# bd2.net
KiCad netlist of a schematic drawn in EAGLE
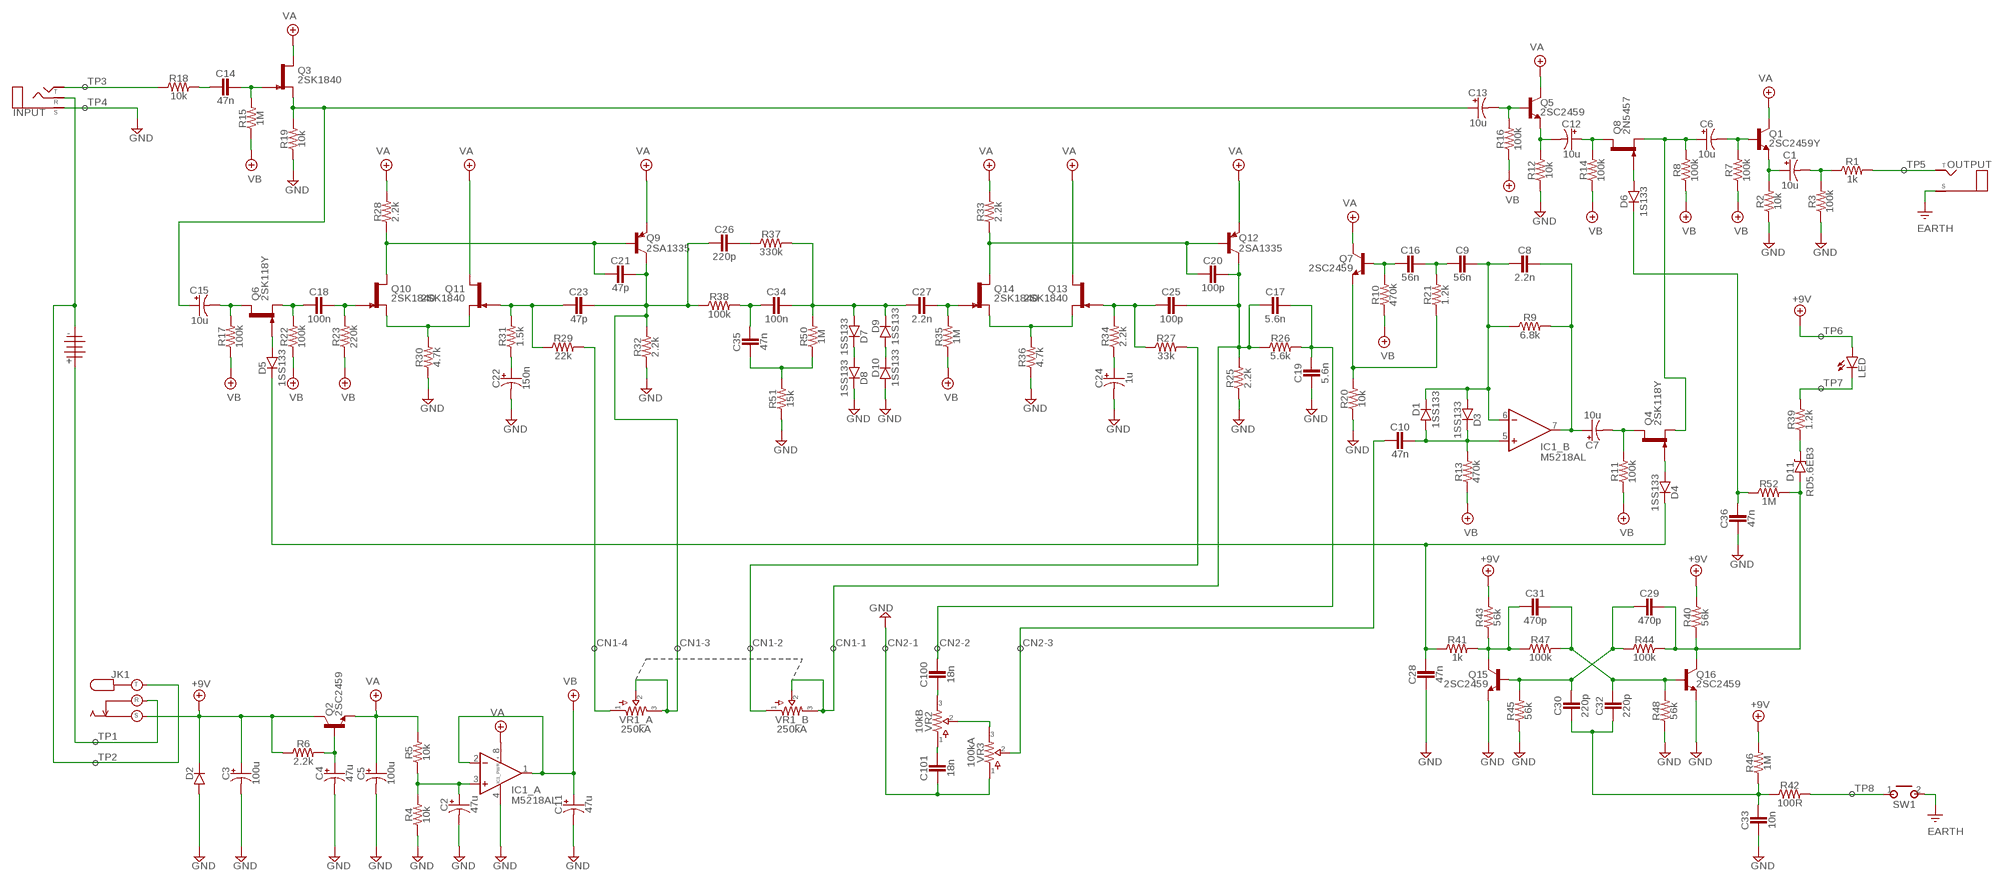
[diagram p0: schematic, sheet 1]

(export (version "E")
  (design (tool "Eeschema 10.0.6"))
  (components
    (comp (ref "BATTERY")
      (value "BATTERY")
      (footprint "eagle-import:TWO_PADS")
      (libsource (lib "eagle-import") (part "BATTERY"))
    )
    (comp (ref "C1")
      (value "10u")
      (footprint "eagle-import:040_020")
      (libsource (lib "eagle-import") (part "0400"))
    )
    (comp (ref "C2")
      (value "47u")
      (footprint "eagle-import:040_020")
      (libsource (lib "eagle-import") (part "0400"))
    )
    (comp (ref "C3")
      (value "100u")
      (footprint "eagle-import:040_020")
      (libsource (lib "eagle-import") (part "0400"))
    )
    (comp (ref "C4")
      (value "47u")
      (footprint "eagle-import:040_020")
      (libsource (lib "eagle-import") (part "0400"))
    )
    (comp (ref "C5")
      (value "100u")
      (footprint "eagle-import:040_020")
      (libsource (lib "eagle-import") (part "0400"))
    )
    (comp (ref "C6")
      (value "10u")
      (footprint "eagle-import:040_020")
      (libsource (lib "eagle-import") (part "0400"))
    )
    (comp (ref "C7")
      (value "10u")
      (footprint "eagle-import:040_020")
      (libsource (lib "eagle-import") (part "0400"))
    )
    (comp (ref "C8")
      (value "2.2n")
      (footprint "eagle-import:BOX_SMALL")
      (libsource (lib "eagle-import") (part "CER/FILMBOX.1"))
    )
    (comp (ref "C9")
      (value "56n")
      (footprint "eagle-import:BOX_SMALL")
      (libsource (lib "eagle-import") (part "CER/FILMBOX.1"))
    )
    (comp (ref "C10")
      (value "47n")
      (footprint "eagle-import:BOX_SMALL")
      (libsource (lib "eagle-import") (part "CER/FILMBOX.1"))
    )
    (comp (ref "C11")
      (value "47u")
      (footprint "eagle-import:040_020")
      (libsource (lib "eagle-import") (part "0400"))
    )
    (comp (ref "C12")
      (value "10u")
      (footprint "eagle-import:040_020")
      (libsource (lib "eagle-import") (part "0400"))
    )
    (comp (ref "C13")
      (value "10u")
      (footprint "eagle-import:040_020")
      (libsource (lib "eagle-import") (part "0400"))
    )
    (comp (ref "C14")
      (value "47n")
      (footprint "eagle-import:BOX_SMALL")
      (libsource (lib "eagle-import") (part "CER/FILMBOX.1"))
    )
    (comp (ref "C15")
      (value "10u")
      (footprint "eagle-import:040_020")
      (libsource (lib "eagle-import") (part "0400"))
    )
    (comp (ref "C16")
      (value "56n")
      (footprint "eagle-import:BOX_SMALL")
      (libsource (lib "eagle-import") (part "CER/FILMBOX.1"))
    )
    (comp (ref "C17")
      (value "5.6n")
      (footprint "eagle-import:BOX_SMALL")
      (libsource (lib "eagle-import") (part "CER/FILMBOX.1"))
    )
    (comp (ref "C18")
      (value "100n")
      (footprint "eagle-import:BOX_SMALL")
      (libsource (lib "eagle-import") (part "CER/FILMBOX.1"))
    )
    (comp (ref "C19")
      (value "5.6n")
      (footprint "eagle-import:BOX_SMALL")
      (libsource (lib "eagle-import") (part "CER/FILMBOX.1"))
    )
    (comp (ref "C20")
      (value "100p")
      (footprint "eagle-import:BOX_SMALL")
      (libsource (lib "eagle-import") (part "CER/FILMBOX.1"))
    )
    (comp (ref "C21")
      (value "47p")
      (footprint "eagle-import:BOX_SMALL")
      (libsource (lib "eagle-import") (part "CER/FILMBOX.1"))
    )
    (comp (ref "C22")
      (value "150n")
      (footprint "eagle-import:040_020")
      (libsource (lib "eagle-import") (part "0400"))
    )
    (comp (ref "C23")
      (value "47p")
      (footprint "eagle-import:BOX_SMALL")
      (libsource (lib "eagle-import") (part "CER/FILMBOX.1"))
    )
    (comp (ref "C24")
      (value "1u")
      (footprint "eagle-import:040_020")
      (libsource (lib "eagle-import") (part "0400"))
    )
    (comp (ref "C25")
      (value "100p")
      (footprint "eagle-import:BOX_SMALL")
      (libsource (lib "eagle-import") (part "CER/FILMBOX.1"))
    )
    (comp (ref "C26")
      (value "220p")
      (footprint "eagle-import:BOX_SMALL")
      (libsource (lib "eagle-import") (part "CER/FILMBOX.1"))
    )
    (comp (ref "C27")
      (value "2.2n")
      (footprint "eagle-import:BOX_SMALL")
      (libsource (lib "eagle-import") (part "CER/FILMBOX.1"))
    )
    (comp (ref "C28")
      (value "47n")
      (footprint "eagle-import:BOX_SMALL")
      (libsource (lib "eagle-import") (part "CER/FILMBOX.1"))
    )
    (comp (ref "C29")
      (value "470p")
      (footprint "eagle-import:BOX_SMALL")
      (libsource (lib "eagle-import") (part "CER/FILMBOX.1"))
    )
    (comp (ref "C30")
      (value "220p")
      (footprint "eagle-import:BOX_SMALL")
      (libsource (lib "eagle-import") (part "CER/FILMBOX.1"))
    )
    (comp (ref "C31")
      (value "470p")
      (footprint "eagle-import:BOX_SMALL")
      (libsource (lib "eagle-import") (part "CER/FILMBOX.1"))
    )
    (comp (ref "C32")
      (value "220p")
      (footprint "eagle-import:BOX_SMALL")
      (libsource (lib "eagle-import") (part "CER/FILMBOX.1"))
    )
    (comp (ref "C33")
      (value "10n")
      (footprint "eagle-import:BOX_SMALL")
      (libsource (lib "eagle-import") (part "CER/FILMBOX.1"))
    )
    (comp (ref "C34")
      (value "100n")
      (footprint "eagle-import:BOX_SMALL")
      (libsource (lib "eagle-import") (part "CER/FILMBOX.1"))
    )
    (comp (ref "C35")
      (value "47n")
      (footprint "eagle-import:BOX_SMALL")
      (libsource (lib "eagle-import") (part "CER/FILMBOX.1"))
    )
    (comp (ref "C36")
      (value "47n")
      (footprint "eagle-import:BOX_SMALL")
      (libsource (lib "eagle-import") (part "CER/FILMBOX.1"))
    )
    (comp (ref "C100")
      (value "18n")
      (footprint "eagle-import:BOX_SMALL")
      (libsource (lib "eagle-import") (part "CER/FILMBOX.1"))
    )
    (comp (ref "C101")
      (value "18n")
      (footprint "eagle-import:BOX_SMALL")
      (libsource (lib "eagle-import") (part "CER/FILMBOX.1"))
    )
    (comp (ref "D1")
      (value "1SS133")
      (footprint "eagle-import:DO41-2")
      (libsource (lib "eagle-import") (part "DO41.2"))
    )
    (comp (ref "D2")
      (value "DO41.2")
      (footprint "eagle-import:DO41-2")
      (libsource (lib "eagle-import") (part "DO41.2"))
    )
    (comp (ref "D3")
      (value "1SS133")
      (footprint "eagle-import:DO41-2")
      (libsource (lib "eagle-import") (part "DO41.2"))
    )
    (comp (ref "D4")
      (value "1SS133")
      (footprint "eagle-import:DO41-2")
      (libsource (lib "eagle-import") (part "DO41.2"))
    )
    (comp (ref "D5")
      (value "1SS133")
      (footprint "eagle-import:DO41-2")
      (libsource (lib "eagle-import") (part "DO41.2"))
    )
    (comp (ref "D6")
      (value "1S133")
      (footprint "eagle-import:DO41-2")
      (libsource (lib "eagle-import") (part "DO41.2"))
    )
    (comp (ref "D7")
      (value "1SS133")
      (footprint "eagle-import:DO41-2")
      (libsource (lib "eagle-import") (part "DO41.2"))
    )
    (comp (ref "D8")
      (value "1SS133")
      (footprint "eagle-import:DO41-2")
      (libsource (lib "eagle-import") (part "DO41.2"))
    )
    (comp (ref "D9")
      (value "1SS133")
      (footprint "eagle-import:DO41-2")
      (libsource (lib "eagle-import") (part "DO41.2"))
    )
    (comp (ref "D10")
      (value "1SS133")
      (footprint "eagle-import:DO41-2")
      (libsource (lib "eagle-import") (part "DO41.2"))
    )
    (comp (ref "D11")
      (value "RD5.6EB3")
      (footprint "eagle-import:DO41-2")
      (libsource (lib "eagle-import") (part "ZENER.2"))
    )
    (comp (ref "IC1")
      (value "M5218AL")
      (footprint "eagle-import:DIL0")
      (libsource (lib "eagle-import") (part "DUALTH"))
    )
    (comp (ref "INPUT")
      (value "STEREO")
      (footprint "eagle-import:STEREO_PCB")
      (libsource (lib "eagle-import") (part "STEREO"))
    )
    (comp (ref "JK1")
      (value "JK1")
      (footprint "eagle-import:DC_KOBICONN")
      (libsource (lib "eagle-import") (part "DC_KOBICONN"))
    )
    (comp (ref "LED")
      (value "LED")
      (footprint "eagle-import:3MM_D")
      (libsource (lib "eagle-import") (part "LED"))
    )
    (comp (ref "OUTPUT")
      (value "MONO")
      (footprint "eagle-import:TWO_PADS")
      (libsource (lib "eagle-import") (part "MONO"))
    )
    (comp (ref "Q1")
      (value "2SC2459Y")
      (footprint "eagle-import:TO92-")
      (libsource (lib "eagle-import") (part "2N3904"))
    )
    (comp (ref "Q2")
      (value "2SC2459")
      (footprint "eagle-import:TO92-")
      (libsource (lib "eagle-import") (part "2N3904"))
    )
    (comp (ref "Q3")
      (value "2SK1840")
      (footprint "eagle-import:TO92-")
      (libsource (lib "eagle-import") (part "2N5457"))
    )
    (comp (ref "Q4")
      (value "2SK118Y")
      (footprint "eagle-import:TO92-")
      (libsource (lib "eagle-import") (part "2N5457"))
    )
    (comp (ref "Q5")
      (value "2SC2459")
      (footprint "eagle-import:TO92-")
      (libsource (lib "eagle-import") (part "2N3904"))
    )
    (comp (ref "Q6")
      (value "2SK118Y")
      (footprint "eagle-import:TO92-")
      (libsource (lib "eagle-import") (part "2N5457"))
    )
    (comp (ref "Q7")
      (value "2SC2459")
      (footprint "eagle-import:TO92-")
      (libsource (lib "eagle-import") (part "2N3904"))
    )
    (comp (ref "Q8")
      (value "2N5457")
      (footprint "eagle-import:TO92-")
      (libsource (lib "eagle-import") (part "2N5457"))
    )
    (comp (ref "Q9")
      (value "2SA1335")
      (footprint "eagle-import:TO92-")
      (libsource (lib "eagle-import") (part "2N3906-"))
    )
    (comp (ref "Q10")
      (value "2SK1840")
      (footprint "eagle-import:TO92-")
      (libsource (lib "eagle-import") (part "2N5457"))
    )
    (comp (ref "Q11")
      (value "2SK1840")
      (footprint "eagle-import:TO92-")
      (libsource (lib "eagle-import") (part "2N5457"))
    )
    (comp (ref "Q12")
      (value "2SA1335")
      (footprint "eagle-import:TO92-")
      (libsource (lib "eagle-import") (part "2N3906-"))
    )
    (comp (ref "Q13")
      (value "2SK1840")
      (footprint "eagle-import:TO92-")
      (libsource (lib "eagle-import") (part "2N5457"))
    )
    (comp (ref "Q14")
      (value "2SK1840")
      (footprint "eagle-import:TO92-")
      (libsource (lib "eagle-import") (part "2N5457"))
    )
    (comp (ref "Q15")
      (value "2SC2459")
      (footprint "eagle-import:TO92-")
      (libsource (lib "eagle-import") (part "2N3904"))
    )
    (comp (ref "Q16")
      (value "2SC2459")
      (footprint "eagle-import:TO92-")
      (libsource (lib "eagle-import") (part "2N3904"))
    )
    (comp (ref "R1")
      (value "1k")
      (footprint "eagle-import:R0207_3")
      (libsource (lib "eagle-import") (part "R_.3B"))
    )
    (comp (ref "R2")
      (value "10k")
      (footprint "eagle-import:R0207_3")
      (libsource (lib "eagle-import") (part "R_.3B"))
    )
    (comp (ref "R3")
      (value "100k")
      (footprint "eagle-import:R0207_3")
      (libsource (lib "eagle-import") (part "R_.3B"))
    )
    (comp (ref "R4")
      (value "10k")
      (footprint "eagle-import:R0207_3")
      (libsource (lib "eagle-import") (part "R_.3B"))
    )
    (comp (ref "R5")
      (value "10k")
      (footprint "eagle-import:R0207_3")
      (libsource (lib "eagle-import") (part "R_.3B"))
    )
    (comp (ref "R6")
      (value "2.2k")
      (footprint "eagle-import:R0207_3")
      (libsource (lib "eagle-import") (part "R_.3B"))
    )
    (comp (ref "R7")
      (value "100k")
      (footprint "eagle-import:R0207_3")
      (libsource (lib "eagle-import") (part "R_.3B"))
    )
    (comp (ref "R8")
      (value "100k")
      (footprint "eagle-import:R0207_3")
      (libsource (lib "eagle-import") (part "R_.3B"))
    )
    (comp (ref "R9")
      (value "6.8k")
      (footprint "eagle-import:R0207_3")
      (libsource (lib "eagle-import") (part "R_.3B"))
    )
    (comp (ref "R10")
      (value "470k")
      (footprint "eagle-import:R0207_3")
      (libsource (lib "eagle-import") (part "R_.3B"))
    )
    (comp (ref "R11")
      (value "100k")
      (footprint "eagle-import:R0207_3")
      (libsource (lib "eagle-import") (part "R_.3B"))
    )
    (comp (ref "R12")
      (value "10k")
      (footprint "eagle-import:R0207_3")
      (libsource (lib "eagle-import") (part "R_.3B"))
    )
    (comp (ref "R13")
      (value "470k")
      (footprint "eagle-import:R0207_3")
      (libsource (lib "eagle-import") (part "R_.3B"))
    )
    (comp (ref "R14")
      (value "100k")
      (footprint "eagle-import:R0207_3")
      (libsource (lib "eagle-import") (part "R_.3B"))
    )
    (comp (ref "R15")
      (value "1M")
      (footprint "eagle-import:R0207_3")
      (libsource (lib "eagle-import") (part "R_.3B"))
    )
    (comp (ref "R16")
      (value "100k")
      (footprint "eagle-import:R0207_3")
      (libsource (lib "eagle-import") (part "R_.3B"))
    )
    (comp (ref "R17")
      (value "100k")
      (footprint "eagle-import:R0207_3")
      (libsource (lib "eagle-import") (part "R_.3B"))
    )
    (comp (ref "R18")
      (value "10k")
      (footprint "eagle-import:R0207_3")
      (libsource (lib "eagle-import") (part "R_.3B"))
    )
    (comp (ref "R19")
      (value "10k")
      (footprint "eagle-import:R0207_3")
      (libsource (lib "eagle-import") (part "R_.3B"))
    )
    (comp (ref "R20")
      (value "10k")
      (footprint "eagle-import:R0207_3")
      (libsource (lib "eagle-import") (part "R_.3B"))
    )
    (comp (ref "R21")
      (value "1.2k")
      (footprint "eagle-import:R0207_3")
      (libsource (lib "eagle-import") (part "R_.3B"))
    )
    (comp (ref "R22")
      (value "100k")
      (footprint "eagle-import:R0207_3")
      (libsource (lib "eagle-import") (part "R_.3B"))
    )
    (comp (ref "R23")
      (value "220k")
      (footprint "eagle-import:R0207_3")
      (libsource (lib "eagle-import") (part "R_.3B"))
    )
    (comp (ref "R25")
      (value "2.2k")
      (footprint "eagle-import:R0207_3")
      (libsource (lib "eagle-import") (part "R_.3B"))
    )
    (comp (ref "R26")
      (value "5.6k")
      (footprint "eagle-import:R0207_3")
      (libsource (lib "eagle-import") (part "R_.3B"))
    )
    (comp (ref "R27")
      (value "33k")
      (footprint "eagle-import:R0207_3")
      (libsource (lib "eagle-import") (part "R_.3B"))
    )
    (comp (ref "R28")
      (value "2.2k")
      (footprint "eagle-import:R0207_3")
      (libsource (lib "eagle-import") (part "R_.3B"))
    )
    (comp (ref "R29")
      (value "22k")
      (footprint "eagle-import:R0207_3")
      (libsource (lib "eagle-import") (part "R_.3B"))
    )
    (comp (ref "R30")
      (value "4.7k")
      (footprint "eagle-import:R0207_3")
      (libsource (lib "eagle-import") (part "R_.3B"))
    )
    (comp (ref "R31")
      (value "1.5k")
      (footprint "eagle-import:R0207_3")
      (libsource (lib "eagle-import") (part "R_.3B"))
    )
    (comp (ref "R32")
      (value "2.2k")
      (footprint "eagle-import:R0207_3")
      (libsource (lib "eagle-import") (part "R_.3B"))
    )
    (comp (ref "R33")
      (value "2.2k")
      (footprint "eagle-import:R0207_3")
      (libsource (lib "eagle-import") (part "R_.3B"))
    )
    (comp (ref "R34")
      (value "2.2k")
      (footprint "eagle-import:R0207_3")
      (libsource (lib "eagle-import") (part "R_.3B"))
    )
    (comp (ref "R35")
      (value "1M")
      (footprint "eagle-import:R0207_3")
      (libsource (lib "eagle-import") (part "R_.3B"))
    )
    (comp (ref "R36")
      (value "4.7k")
      (footprint "eagle-import:R0207_3")
      (libsource (lib "eagle-import") (part "R_.3B"))
    )
    (comp (ref "R37")
      (value "330k")
      (footprint "eagle-import:R0207_3")
      (libsource (lib "eagle-import") (part "R_.3B"))
    )
    (comp (ref "R38")
      (value "100k")
      (footprint "eagle-import:R0207_3")
      (libsource (lib "eagle-import") (part "R_.3B"))
    )
    (comp (ref "R39")
      (value "1.2k")
      (footprint "eagle-import:R0207_3")
      (libsource (lib "eagle-import") (part "R_.3B"))
    )
    (comp (ref "R40")
      (value "56k")
      (footprint "eagle-import:R0207_3")
      (libsource (lib "eagle-import") (part "R_.3B"))
    )
    (comp (ref "R41")
      (value "1k")
      (footprint "eagle-import:R0207_3")
      (libsource (lib "eagle-import") (part "R_.3B"))
    )
    (comp (ref "R42")
      (value "100R")
      (footprint "eagle-import:R0207_3")
      (libsource (lib "eagle-import") (part "R_.3B"))
    )
    (comp (ref "R43")
      (value "56k")
      (footprint "eagle-import:R0207_3")
      (libsource (lib "eagle-import") (part "R_.3B"))
    )
    (comp (ref "R44")
      (value "100k")
      (footprint "eagle-import:R0207_3")
      (libsource (lib "eagle-import") (part "R_.3B"))
    )
    (comp (ref "R45")
      (value "56k")
      (footprint "eagle-import:R0207_3")
      (libsource (lib "eagle-import") (part "R_.3B"))
    )
    (comp (ref "R46")
      (value "1M")
      (footprint "eagle-import:R0207_3")
      (libsource (lib "eagle-import") (part "R_.3B"))
    )
    (comp (ref "R47")
      (value "100k")
      (footprint "eagle-import:R0207_3")
      (libsource (lib "eagle-import") (part "R_.3B"))
    )
    (comp (ref "R48")
      (value "56k")
      (footprint "eagle-import:R0207_3")
      (libsource (lib "eagle-import") (part "R_.3B"))
    )
    (comp (ref "R50")
      (value "1M")
      (footprint "eagle-import:R0207_3")
      (libsource (lib "eagle-import") (part "R_.3B"))
    )
    (comp (ref "R51")
      (value "15k")
      (footprint "eagle-import:R0207_3")
      (libsource (lib "eagle-import") (part "R_.3B"))
    )
    (comp (ref "R52")
      (value "1M")
      (footprint "eagle-import:R0207_3")
      (libsource (lib "eagle-import") (part "R_.3B"))
    )
    (comp (ref "SW1")
      (value "MOMENTARY")
      (footprint "eagle-import:SPST")
      (libsource (lib "eagle-import") (part "MOMENTARY"))
    )
    (comp (ref "VR1")
      (value "250kA")
      (footprint "eagle-import:16MM_DUAL")
      (libsource (lib "eagle-import") (part "DUALGANG16MM_DUAL"))
    )
    (comp (ref "VR2")
      (value "10kB")
      (footprint "eagle-import:16MM")
      (libsource (lib "eagle-import") (part "POTS16MM"))
    )
    (comp (ref "VR3")
      (value "100kA")
      (footprint "eagle-import:16MM")
      (libsource (lib "eagle-import") (part "POTS16MM"))
    )
  )
  (nets
    (net (code "1") (name "+9V") (class "Default")
      (node (ref "C3") (pin "+") (pinfunction "+_+") (pintype "passive"))
      (node (ref "D2") (pin "C") (pinfunction "C_C") (pintype "passive"))
      (node (ref "JK1") (pin "S") (pinfunction "S_S") (pintype "bidirectional"))
      (node (ref "LED") (pin "ANODE") (pinfunction "A_ANODE") (pintype "passive"))
      (node (ref "Q2") (pin "1") (pinfunction "C_1") (pintype "passive"))
      (node (ref "R40") (pin "2") (pinfunction "2_2") (pintype "passive"))
      (node (ref "R43") (pin "2") (pinfunction "2_2") (pintype "passive"))
      (node (ref "R46") (pin "2") (pinfunction "2_2") (pintype "passive"))
      (node (ref "R6") (pin "1") (pinfunction "1_1") (pintype "passive"))
    )
    (net (code "2") (name "EARTH") (class "Default")
      (node (ref "C101") (pin "2") (pinfunction "2_2") (pintype "passive"))
      (node (ref "C11") (pin "-") (pinfunction "-_-") (pintype "passive"))
      (node (ref "C19") (pin "2") (pinfunction "2_2") (pintype "passive"))
      (node (ref "C2") (pin "-") (pinfunction "-_-") (pintype "passive"))
      (node (ref "C22") (pin "-") (pinfunction "-_-") (pintype "passive"))
      (node (ref "C24") (pin "-") (pinfunction "-_-") (pintype "passive"))
      (node (ref "C28") (pin "2") (pinfunction "2_2") (pintype "passive"))
      (node (ref "C3") (pin "-") (pinfunction "-_-") (pintype "passive"))
      (node (ref "C33") (pin "2") (pinfunction "2_2") (pintype "passive"))
      (node (ref "C36") (pin "2") (pinfunction "2_2") (pintype "passive"))
      (node (ref "C4") (pin "-") (pinfunction "-_-") (pintype "passive"))
      (node (ref "C5") (pin "-") (pinfunction "-_-") (pintype "passive"))
      (node (ref "D10") (pin "A") (pinfunction "A_A") (pintype "passive"))
      (node (ref "D2") (pin "A") (pinfunction "A_A") (pintype "passive"))
      (node (ref "D8") (pin "C") (pinfunction "C_C") (pintype "passive"))
      (node (ref "IC1") (pin "4") (pinfunction "V-_4") (pintype "power_in"))
      (node (ref "INPUT") (pin "P$1") (pinfunction "S_P$1") (pintype "passive"))
      (node (ref "OUTPUT") (pin "S") (pinfunction "SLEEVE_S") (pintype "passive"))
      (node (ref "Q15") (pin "3") (pinfunction "E_3") (pintype "passive"))
      (node (ref "Q16") (pin "3") (pinfunction "E_3") (pintype "passive"))
      (node (ref "R12") (pin "1") (pinfunction "1_1") (pintype "passive"))
      (node (ref "R19") (pin "1") (pinfunction "1_1") (pintype "passive"))
      (node (ref "R2") (pin "1") (pinfunction "1_1") (pintype "passive"))
      (node (ref "R20") (pin "1") (pinfunction "1_1") (pintype "passive"))
      (node (ref "R25") (pin "1") (pinfunction "1_1") (pintype "passive"))
      (node (ref "R3") (pin "1") (pinfunction "1_1") (pintype "passive"))
      (node (ref "R30") (pin "1") (pinfunction "1_1") (pintype "passive"))
      (node (ref "R32") (pin "1") (pinfunction "1_1") (pintype "passive"))
      (node (ref "R36") (pin "1") (pinfunction "1_1") (pintype "passive"))
      (node (ref "R4") (pin "1") (pinfunction "1_1") (pintype "passive"))
      (node (ref "R45") (pin "1") (pinfunction "1_1") (pintype "passive"))
      (node (ref "R48") (pin "1") (pinfunction "1_1") (pintype "passive"))
      (node (ref "R51") (pin "1") (pinfunction "1_1") (pintype "passive"))
      (node (ref "SW1") (pin "2") (pinfunction "S_2") (pintype "passive"))
      (node (ref "VR3") (pin "1") (pinfunction "1_1") (pintype "passive"))
    )
    (net (code "3") (name "Net-(BATTERY-P$1)") (class "Default")
      (node (ref "BATTERY") (pin "T") (pinfunction "P$1_T") (pintype "bidirectional"))
      (node (ref "JK1") (pin "R") (pinfunction "R_R") (pintype "bidirectional"))
    )
    (net (code "4") (name "Net-(BATTERY-P$2)") (class "Default")
      (node (ref "BATTERY") (pin "S") (pinfunction "P$2_S") (pintype "bidirectional"))
      (node (ref "INPUT") (pin "P$2") (pinfunction "R_P$2") (pintype "passive"))
      (node (ref "JK1") (pin "T") (pinfunction "T_T") (pintype "bidirectional"))
    )
    (net (code "5") (name "Net-(C1-Pad-)") (class "Default")
      (node (ref "C1") (pin "-") (pinfunction "-_-") (pintype "passive"))
      (node (ref "R1") (pin "1") (pinfunction "1_1") (pintype "passive"))
      (node (ref "R3") (pin "2") (pinfunction "2_2") (pintype "passive"))
    )
    (net (code "6") (name "Net-(C10-Pad2)") (class "Default")
      (node (ref "C10") (pin "2") (pinfunction "2_2") (pintype "passive"))
      (node (ref "VR3") (pin "2") (pinfunction "2_2") (pintype "passive"))
    )
    (net (code "7") (name "Net-(C14-Pad2)") (class "Default")
      (node (ref "C14") (pin "2") (pinfunction "2_2") (pintype "passive"))
      (node (ref "R18") (pin "2") (pinfunction "2_2") (pintype "passive"))
    )
    (net (code "8") (name "Net-(C16-Pad1)") (class "Default")
      (node (ref "C16") (pin "1") (pinfunction "1_1") (pintype "passive"))
      (node (ref "C9") (pin "2") (pinfunction "2_2") (pintype "passive"))
      (node (ref "R21") (pin "2") (pinfunction "2_2") (pintype "passive"))
    )
    (net (code "9") (name "Net-(C22-Pad+)") (class "Default")
      (node (ref "C22") (pin "+") (pinfunction "+_+") (pintype "passive"))
      (node (ref "R31") (pin "1") (pinfunction "1_1") (pintype "passive"))
    )
    (net (code "10") (name "Net-(C24-Pad+)") (class "Default")
      (node (ref "C24") (pin "+") (pinfunction "+_+") (pintype "passive"))
      (node (ref "R34") (pin "1") (pinfunction "1_1") (pintype "passive"))
    )
    (net (code "11") (name "Net-(C26-Pad1)") (class "Default")
      (node (ref "C26") (pin "1") (pinfunction "1_1") (pintype "passive"))
      (node (ref "R37") (pin "1") (pinfunction "1_1") (pintype "passive"))
    )
    (net (code "12") (name "Net-(C27-Pad2)") (class "Default")
      (node (ref "C27") (pin "2") (pinfunction "2_2") (pintype "passive"))
      (node (ref "C34") (pin "1") (pinfunction "1_1") (pintype "passive"))
      (node (ref "D7") (pin "A") (pinfunction "A_A") (pintype "passive"))
      (node (ref "D9") (pin "C") (pinfunction "C_C") (pintype "passive"))
      (node (ref "R37") (pin "2") (pinfunction "2_2") (pintype "passive"))
      (node (ref "R50") (pin "2") (pinfunction "2_2") (pintype "passive"))
    )
    (net (code "13") (name "Net-(C28-Pad1)") (class "Default")
      (node (ref "C28") (pin "1") (pinfunction "1_1") (pintype "passive"))
      (node (ref "D4") (pin "C") (pinfunction "C_C") (pintype "passive"))
      (node (ref "D5") (pin "C") (pinfunction "C_C") (pintype "passive"))
      (node (ref "R41") (pin "1") (pinfunction "1_1") (pintype "passive"))
    )
    (net (code "14") (name "Net-(C30-Pad2)") (class "Default")
      (node (ref "C30") (pin "2") (pinfunction "2_2") (pintype "passive"))
      (node (ref "C32") (pin "2") (pinfunction "2_2") (pintype "passive"))
      (node (ref "C33") (pin "1") (pinfunction "1_1") (pintype "passive"))
      (node (ref "R42") (pin "1") (pinfunction "1_1") (pintype "passive"))
      (node (ref "R46") (pin "1") (pinfunction "1_1") (pintype "passive"))
    )
    (net (code "15") (name "Net-(C34-Pad2)") (class "Default")
      (node (ref "C34") (pin "2") (pinfunction "2_2") (pintype "passive"))
      (node (ref "C35") (pin "1") (pinfunction "1_1") (pintype "passive"))
      (node (ref "R38") (pin "2") (pinfunction "2_2") (pintype "passive"))
    )
    (net (code "16") (name "Net-(C35-Pad2)") (class "Default")
      (node (ref "C35") (pin "2") (pinfunction "2_2") (pintype "passive"))
      (node (ref "R50") (pin "1") (pinfunction "1_1") (pintype "passive"))
      (node (ref "R51") (pin "2") (pinfunction "2_2") (pintype "passive"))
    )
    (net (code "17") (name "Net-(C36-Pad1)") (class "Default")
      (node (ref "C36") (pin "1") (pinfunction "1_1") (pintype "passive"))
      (node (ref "D6") (pin "C") (pinfunction "C_C") (pintype "passive"))
      (node (ref "R52") (pin "1") (pinfunction "1_1") (pintype "passive"))
    )
    (net (code "18") (name "Net-(C100-Pad1)") (class "Default")
      (node (ref "C100") (pin "1") (pinfunction "1_1") (pintype "passive"))
      (node (ref "C17") (pin "1") (pinfunction "1_1") (pintype "passive"))
      (node (ref "C19") (pin "1") (pinfunction "1_1") (pintype "passive"))
      (node (ref "R26") (pin "2") (pinfunction "2_2") (pintype "passive"))
    )
    (net (code "19") (name "Net-(C100-Pad2)") (class "Default")
      (node (ref "C100") (pin "2") (pinfunction "2_2") (pintype "passive"))
      (node (ref "VR2") (pin "3") (pinfunction "3_3") (pintype "passive"))
    )
    (net (code "20") (name "Net-(C101-Pad1)") (class "Default")
      (node (ref "C101") (pin "1") (pinfunction "1_1") (pintype "passive"))
      (node (ref "VR2") (pin "1") (pinfunction "1_1") (pintype "passive"))
    )
    (net (code "21") (name "Net-(D7-PadC)") (class "Default")
      (node (ref "D7") (pin "C") (pinfunction "C_C") (pintype "passive"))
      (node (ref "D8") (pin "A") (pinfunction "A_A") (pintype "passive"))
    )
    (net (code "22") (name "Net-(D10-PadC)") (class "Default")
      (node (ref "D10") (pin "C") (pinfunction "C_C") (pintype "passive"))
      (node (ref "D9") (pin "A") (pinfunction "A_A") (pintype "passive"))
    )
    (net (code "23") (name "Net-(D11-PadC)") (class "Default")
      (node (ref "D11") (pin "C") (pinfunction "C_C") (pintype "passive"))
      (node (ref "R39") (pin "1") (pinfunction "1_1") (pintype "passive"))
    )
    (net (code "24") (name "Net-(IC1A-+IN)") (class "Default")
      (node (ref "C2") (pin "+") (pinfunction "+_+") (pintype "passive"))
      (node (ref "IC1") (pin "3") (pinfunction "+IN_3") (pintype "input"))
      (node (ref "R4") (pin "2") (pinfunction "2_2") (pintype "passive"))
      (node (ref "R5") (pin "1") (pinfunction "1_1") (pintype "passive"))
    )
    (net (code "25") (name "Net-(IC1B-+IN)") (class "Default")
      (node (ref "C10") (pin "1") (pinfunction "1_1") (pintype "passive"))
      (node (ref "D1") (pin "A") (pinfunction "A_A") (pintype "passive"))
      (node (ref "D3") (pin "C") (pinfunction "C_C") (pintype "passive"))
      (node (ref "IC1") (pin "5") (pinfunction "+IN_5") (pintype "input"))
      (node (ref "R13") (pin "2") (pinfunction "2_2") (pintype "passive"))
    )
    (net (code "26") (name "Net-(IC1B--IN)") (class "Default")
      (node (ref "C8") (pin "2") (pinfunction "2_2") (pintype "passive"))
      (node (ref "C9") (pin "1") (pinfunction "1_1") (pintype "passive"))
      (node (ref "D1") (pin "C") (pinfunction "C_C") (pintype "passive"))
      (node (ref "D3") (pin "A") (pinfunction "A_A") (pintype "passive"))
      (node (ref "IC1") (pin "6") (pinfunction "-IN_6") (pintype "input"))
      (node (ref "R9") (pin "1") (pinfunction "1_1") (pintype "passive"))
    )
    (net (code "27") (name "Net-(IC1B-OUT)") (class "Default")
      (node (ref "C7") (pin "+") (pinfunction "+_+") (pintype "passive"))
      (node (ref "C8") (pin "1") (pinfunction "1_1") (pintype "passive"))
      (node (ref "IC1") (pin "7") (pinfunction "OUT_7") (pintype "output"))
      (node (ref "R9") (pin "2") (pinfunction "2_2") (pintype "passive"))
    )
    (net (code "28") (name "Net-(INPUT-T)") (class "Default")
      (node (ref "INPUT") (pin "P$3") (pinfunction "T_P$3") (pintype "passive"))
      (node (ref "R18") (pin "1") (pinfunction "1_1") (pintype "passive"))
    )
    (net (code "29") (name "Net-(LED-C)") (class "Default")
      (node (ref "LED") (pin "P$1") (pinfunction "C_P$1") (pintype "passive"))
      (node (ref "R39") (pin "2") (pinfunction "2_2") (pintype "passive"))
    )
    (net (code "30") (name "Net-(OUTPUT-TIP)") (class "Default")
      (node (ref "OUTPUT") (pin "T") (pinfunction "TIP_T") (pintype "passive"))
      (node (ref "R1") (pin "2") (pinfunction "2_2") (pintype "passive"))
    )
    (net (code "31") (name "Net-(Q1-B)") (class "Default")
      (node (ref "C6") (pin "-") (pinfunction "-_-") (pintype "passive"))
      (node (ref "Q1") (pin "2") (pinfunction "B_2") (pintype "passive"))
      (node (ref "R7") (pin "2") (pinfunction "2_2") (pintype "passive"))
    )
    (net (code "32") (name "Net-(Q1-E)") (class "Default")
      (node (ref "C1") (pin "+") (pinfunction "+_+") (pintype "passive"))
      (node (ref "Q1") (pin "3") (pinfunction "E_3") (pintype "passive"))
      (node (ref "R2") (pin "2") (pinfunction "2_2") (pintype "passive"))
    )
    (net (code "33") (name "Net-(Q2-B)") (class "Default")
      (node (ref "C4") (pin "+") (pinfunction "+_+") (pintype "passive"))
      (node (ref "Q2") (pin "2") (pinfunction "B_2") (pintype "passive"))
      (node (ref "R6") (pin "2") (pinfunction "2_2") (pintype "passive"))
    )
    (net (code "34") (name "Net-(Q3-G)") (class "Default")
      (node (ref "C14") (pin "1") (pinfunction "1_1") (pintype "passive"))
      (node (ref "Q3") (pin "1") (pinfunction "G_1") (pintype "passive"))
      (node (ref "R15") (pin "2") (pinfunction "2_2") (pintype "passive"))
    )
    (net (code "35") (name "Net-(Q3-S)") (class "Default")
      (node (ref "C13") (pin "+") (pinfunction "+_+") (pintype "passive"))
      (node (ref "C15") (pin "+") (pinfunction "+_+") (pintype "passive"))
      (node (ref "Q3") (pin "2") (pinfunction "S_2") (pintype "passive"))
      (node (ref "R19") (pin "2") (pinfunction "2_2") (pintype "passive"))
    )
    (net (code "36") (name "Net-(Q4-D)") (class "Default")
      (node (ref "C7") (pin "-") (pinfunction "-_-") (pintype "passive"))
      (node (ref "Q4") (pin "3") (pinfunction "D_3") (pintype "passive"))
      (node (ref "R11") (pin "2") (pinfunction "2_2") (pintype "passive"))
    )
    (net (code "37") (name "Net-(Q4-G)") (class "Default")
      (node (ref "D4") (pin "A") (pinfunction "A_A") (pintype "passive"))
      (node (ref "Q4") (pin "1") (pinfunction "G_1") (pintype "passive"))
    )
    (net (code "38") (name "Net-(Q4-S)") (class "Default")
      (node (ref "C6") (pin "+") (pinfunction "+_+") (pintype "passive"))
      (node (ref "Q4") (pin "2") (pinfunction "S_2") (pintype "passive"))
      (node (ref "Q8") (pin "2") (pinfunction "S_2") (pintype "passive"))
      (node (ref "R8") (pin "2") (pinfunction "2_2") (pintype "passive"))
    )
    (net (code "39") (name "Net-(Q5-B)") (class "Default")
      (node (ref "C13") (pin "-") (pinfunction "-_-") (pintype "passive"))
      (node (ref "Q5") (pin "2") (pinfunction "B_2") (pintype "passive"))
      (node (ref "R16") (pin "2") (pinfunction "2_2") (pintype "passive"))
    )
    (net (code "40") (name "Net-(Q5-E)") (class "Default")
      (node (ref "C12") (pin "-") (pinfunction "-_-") (pintype "passive"))
      (node (ref "Q5") (pin "3") (pinfunction "E_3") (pintype "passive"))
      (node (ref "R12") (pin "2") (pinfunction "2_2") (pintype "passive"))
    )
    (net (code "41") (name "Net-(Q6-D)") (class "Default")
      (node (ref "C15") (pin "-") (pinfunction "-_-") (pintype "passive"))
      (node (ref "Q6") (pin "3") (pinfunction "D_3") (pintype "passive"))
      (node (ref "R17") (pin "2") (pinfunction "2_2") (pintype "passive"))
    )
    (net (code "42") (name "Net-(Q6-G)") (class "Default")
      (node (ref "D5") (pin "A") (pinfunction "A_A") (pintype "passive"))
      (node (ref "Q6") (pin "1") (pinfunction "G_1") (pintype "passive"))
    )
    (net (code "43") (name "Net-(Q6-S)") (class "Default")
      (node (ref "C18") (pin "2") (pinfunction "2_2") (pintype "passive"))
      (node (ref "Q6") (pin "2") (pinfunction "S_2") (pintype "passive"))
      (node (ref "R22") (pin "2") (pinfunction "2_2") (pintype "passive"))
    )
    (net (code "44") (name "Net-(Q7-B)") (class "Default")
      (node (ref "C16") (pin "2") (pinfunction "2_2") (pintype "passive"))
      (node (ref "Q7") (pin "2") (pinfunction "B_2") (pintype "passive"))
      (node (ref "R10") (pin "2") (pinfunction "2_2") (pintype "passive"))
    )
    (net (code "45") (name "Net-(Q7-E)") (class "Default")
      (node (ref "Q7") (pin "3") (pinfunction "E_3") (pintype "passive"))
      (node (ref "R20") (pin "2") (pinfunction "2_2") (pintype "passive"))
      (node (ref "R21") (pin "1") (pinfunction "1_1") (pintype "passive"))
    )
    (net (code "46") (name "Net-(Q8-D)") (class "Default")
      (node (ref "C12") (pin "+") (pinfunction "+_+") (pintype "passive"))
      (node (ref "Q8") (pin "3") (pinfunction "D_3") (pintype "passive"))
      (node (ref "R14") (pin "2") (pinfunction "2_2") (pintype "passive"))
    )
    (net (code "47") (name "Net-(Q8-G)") (class "Default")
      (node (ref "D6") (pin "A") (pinfunction "A_A") (pintype "passive"))
      (node (ref "Q8") (pin "1") (pinfunction "G_1") (pintype "passive"))
    )
    (net (code "48") (name "Net-(Q9-C)") (class "Default")
      (node (ref "C21") (pin "1") (pinfunction "1_1") (pintype "passive"))
      (node (ref "C23") (pin "1") (pinfunction "1_1") (pintype "passive"))
      (node (ref "C26") (pin "2") (pinfunction "2_2") (pintype "passive"))
      (node (ref "Q9") (pin "1") (pinfunction "C_1") (pintype "passive"))
      (node (ref "R32") (pin "2") (pinfunction "2_2") (pintype "passive"))
      (node (ref "R38") (pin "1") (pinfunction "1_1") (pintype "passive"))
      (node (ref "VR1") (pin "2") (pinfunction "2_2") (pintype "passive"))
      (node (ref "VR1") (pin "3") (pinfunction "3_3") (pintype "passive"))
    )
    (net (code "49") (name "Net-(Q10-D)") (class "Default")
      (node (ref "C21") (pin "2") (pinfunction "2_2") (pintype "passive"))
      (node (ref "Q10") (pin "3") (pinfunction "D_3") (pintype "passive"))
      (node (ref "Q9") (pin "2") (pinfunction "B_2") (pintype "passive"))
      (node (ref "R28") (pin "1") (pinfunction "1_1") (pintype "passive"))
    )
    (net (code "50") (name "Net-(Q10-G)") (class "Default")
      (node (ref "C18") (pin "1") (pinfunction "1_1") (pintype "passive"))
      (node (ref "Q10") (pin "1") (pinfunction "G_1") (pintype "passive"))
      (node (ref "R23") (pin "2") (pinfunction "2_2") (pintype "passive"))
    )
    (net (code "51") (name "Net-(Q10-S)") (class "Default")
      (node (ref "Q10") (pin "2") (pinfunction "S_2") (pintype "passive"))
      (node (ref "Q11") (pin "2") (pinfunction "S_2") (pintype "passive"))
      (node (ref "R30") (pin "2") (pinfunction "2_2") (pintype "passive"))
    )
    (net (code "52") (name "Net-(Q11-G)") (class "Default")
      (node (ref "C23") (pin "2") (pinfunction "2_2") (pintype "passive"))
      (node (ref "Q11") (pin "1") (pinfunction "G_1") (pintype "passive"))
      (node (ref "R29") (pin "1") (pinfunction "1_1") (pintype "passive"))
      (node (ref "R31") (pin "2") (pinfunction "2_2") (pintype "passive"))
    )
    (net (code "53") (name "Net-(Q12-B)") (class "Default")
      (node (ref "C20") (pin "2") (pinfunction "2_2") (pintype "passive"))
      (node (ref "Q12") (pin "2") (pinfunction "B_2") (pintype "passive"))
      (node (ref "Q14") (pin "3") (pinfunction "D_3") (pintype "passive"))
      (node (ref "R33") (pin "1") (pinfunction "1_1") (pintype "passive"))
    )
    (net (code "54") (name "Net-(Q12-C)") (class "Default")
      (node (ref "C17") (pin "2") (pinfunction "2_2") (pintype "passive"))
      (node (ref "C20") (pin "1") (pinfunction "1_1") (pintype "passive"))
      (node (ref "C25") (pin "1") (pinfunction "1_1") (pintype "passive"))
      (node (ref "Q12") (pin "1") (pinfunction "C_1") (pintype "passive"))
      (node (ref "R25") (pin "2") (pinfunction "2_2") (pintype "passive"))
      (node (ref "R26") (pin "1") (pinfunction "1_1") (pintype "passive"))
      (node (ref "VR1") (pin "5") (pinfunction "2_5") (pintype "passive"))
      (node (ref "VR1") (pin "6") (pinfunction "3_6") (pintype "passive"))
    )
    (net (code "55") (name "Net-(Q13-G)") (class "Default")
      (node (ref "C25") (pin "2") (pinfunction "2_2") (pintype "passive"))
      (node (ref "Q13") (pin "1") (pinfunction "G_1") (pintype "passive"))
      (node (ref "R27") (pin "1") (pinfunction "1_1") (pintype "passive"))
      (node (ref "R34") (pin "2") (pinfunction "2_2") (pintype "passive"))
    )
    (net (code "56") (name "Net-(Q13-S)") (class "Default")
      (node (ref "Q13") (pin "2") (pinfunction "S_2") (pintype "passive"))
      (node (ref "Q14") (pin "2") (pinfunction "S_2") (pintype "passive"))
      (node (ref "R36") (pin "2") (pinfunction "2_2") (pintype "passive"))
    )
    (net (code "57") (name "Net-(Q14-G)") (class "Default")
      (node (ref "C27") (pin "1") (pinfunction "1_1") (pintype "passive"))
      (node (ref "Q14") (pin "1") (pinfunction "G_1") (pintype "passive"))
      (node (ref "R35") (pin "2") (pinfunction "2_2") (pintype "passive"))
    )
    (net (code "58") (name "Net-(Q15-B)") (class "Default")
      (node (ref "C29") (pin "2") (pinfunction "2_2") (pintype "passive"))
      (node (ref "C30") (pin "1") (pinfunction "1_1") (pintype "passive"))
      (node (ref "Q15") (pin "2") (pinfunction "B_2") (pintype "passive"))
      (node (ref "R44") (pin "1") (pinfunction "1_1") (pintype "passive"))
      (node (ref "R45") (pin "2") (pinfunction "2_2") (pintype "passive"))
    )
    (net (code "59") (name "Net-(Q15-C)") (class "Default")
      (node (ref "C31") (pin "2") (pinfunction "2_2") (pintype "passive"))
      (node (ref "Q15") (pin "1") (pinfunction "C_1") (pintype "passive"))
      (node (ref "R41") (pin "2") (pinfunction "2_2") (pintype "passive"))
      (node (ref "R43") (pin "1") (pinfunction "1_1") (pintype "passive"))
      (node (ref "R47") (pin "1") (pinfunction "1_1") (pintype "passive"))
    )
    (net (code "60") (name "Net-(Q16-B)") (class "Default")
      (node (ref "C31") (pin "1") (pinfunction "1_1") (pintype "passive"))
      (node (ref "C32") (pin "1") (pinfunction "1_1") (pintype "passive"))
      (node (ref "Q16") (pin "2") (pinfunction "B_2") (pintype "passive"))
      (node (ref "R47") (pin "2") (pinfunction "2_2") (pintype "passive"))
      (node (ref "R48") (pin "2") (pinfunction "2_2") (pintype "passive"))
    )
    (net (code "61") (name "Net-(Q16-C)") (class "Default")
      (node (ref "C29") (pin "1") (pinfunction "1_1") (pintype "passive"))
      (node (ref "D11") (pin "A") (pinfunction "A_A") (pintype "passive"))
      (node (ref "Q16") (pin "1") (pinfunction "C_1") (pintype "passive"))
      (node (ref "R40") (pin "1") (pinfunction "1_1") (pintype "passive"))
      (node (ref "R44") (pin "2") (pinfunction "2_2") (pintype "passive"))
      (node (ref "R52") (pin "2") (pinfunction "2_2") (pintype "passive"))
    )
    (net (code "62") (name "Net-(R29-Pad2)") (class "Default")
      (node (ref "R29") (pin "2") (pinfunction "2_2") (pintype "passive"))
      (node (ref "VR1") (pin "1") (pinfunction "1_1") (pintype "passive"))
    )
    (net (code "63") (name "Net-(SW1-P)") (class "Default")
      (node (ref "R42") (pin "2") (pinfunction "2_2") (pintype "passive"))
      (node (ref "SW1") (pin "1") (pinfunction "P_1") (pintype "passive"))
    )
    (net (code "64") (name "Net-(VR1B-1)") (class "Default")
      (node (ref "R27") (pin "2") (pinfunction "2_2") (pintype "passive"))
      (node (ref "VR1") (pin "4") (pinfunction "1_4") (pintype "passive"))
    )
    (net (code "65") (name "Net-(VR2-Pad2)") (class "Default")
      (node (ref "VR2") (pin "2") (pinfunction "2_2") (pintype "passive"))
      (node (ref "VR3") (pin "3") (pinfunction "3_3") (pintype "passive"))
    )
    (net (code "66") (name "VA") (class "Default")
      (node (ref "C5") (pin "+") (pinfunction "+_+") (pintype "passive"))
      (node (ref "IC1") (pin "8") (pinfunction "V+_8") (pintype "power_in"))
      (node (ref "Q1") (pin "1") (pinfunction "C_1") (pintype "passive"))
      (node (ref "Q11") (pin "3") (pinfunction "D_3") (pintype "passive"))
      (node (ref "Q12") (pin "3") (pinfunction "E_3") (pintype "passive"))
      (node (ref "Q13") (pin "3") (pinfunction "D_3") (pintype "passive"))
      (node (ref "Q2") (pin "3") (pinfunction "E_3") (pintype "passive"))
      (node (ref "Q3") (pin "3") (pinfunction "D_3") (pintype "passive"))
      (node (ref "Q5") (pin "1") (pinfunction "C_1") (pintype "passive"))
      (node (ref "Q7") (pin "1") (pinfunction "C_1") (pintype "passive"))
      (node (ref "Q9") (pin "3") (pinfunction "E_3") (pintype "passive"))
      (node (ref "R28") (pin "2") (pinfunction "2_2") (pintype "passive"))
      (node (ref "R33") (pin "2") (pinfunction "2_2") (pintype "passive"))
      (node (ref "R5") (pin "2") (pinfunction "2_2") (pintype "passive"))
    )
    (net (code "67") (name "VB") (class "Default")
      (node (ref "C11") (pin "+") (pinfunction "+_+") (pintype "passive"))
      (node (ref "IC1") (pin "1") (pinfunction "OUT_1") (pintype "output"))
      (node (ref "IC1") (pin "2") (pinfunction "-IN_2") (pintype "input"))
      (node (ref "R10") (pin "1") (pinfunction "1_1") (pintype "passive"))
      (node (ref "R11") (pin "1") (pinfunction "1_1") (pintype "passive"))
      (node (ref "R13") (pin "1") (pinfunction "1_1") (pintype "passive"))
      (node (ref "R14") (pin "1") (pinfunction "1_1") (pintype "passive"))
      (node (ref "R15") (pin "1") (pinfunction "1_1") (pintype "passive"))
      (node (ref "R16") (pin "1") (pinfunction "1_1") (pintype "passive"))
      (node (ref "R17") (pin "1") (pinfunction "1_1") (pintype "passive"))
      (node (ref "R22") (pin "1") (pinfunction "1_1") (pintype "passive"))
      (node (ref "R23") (pin "1") (pinfunction "1_1") (pintype "passive"))
      (node (ref "R35") (pin "1") (pinfunction "1_1") (pintype "passive"))
      (node (ref "R7") (pin "1") (pinfunction "1_1") (pintype "passive"))
      (node (ref "R8") (pin "1") (pinfunction "1_1") (pintype "passive"))
    )
  )
)
